# pcm5102_dac.net
KiCad netlist of a schematic drawn in EAGLE
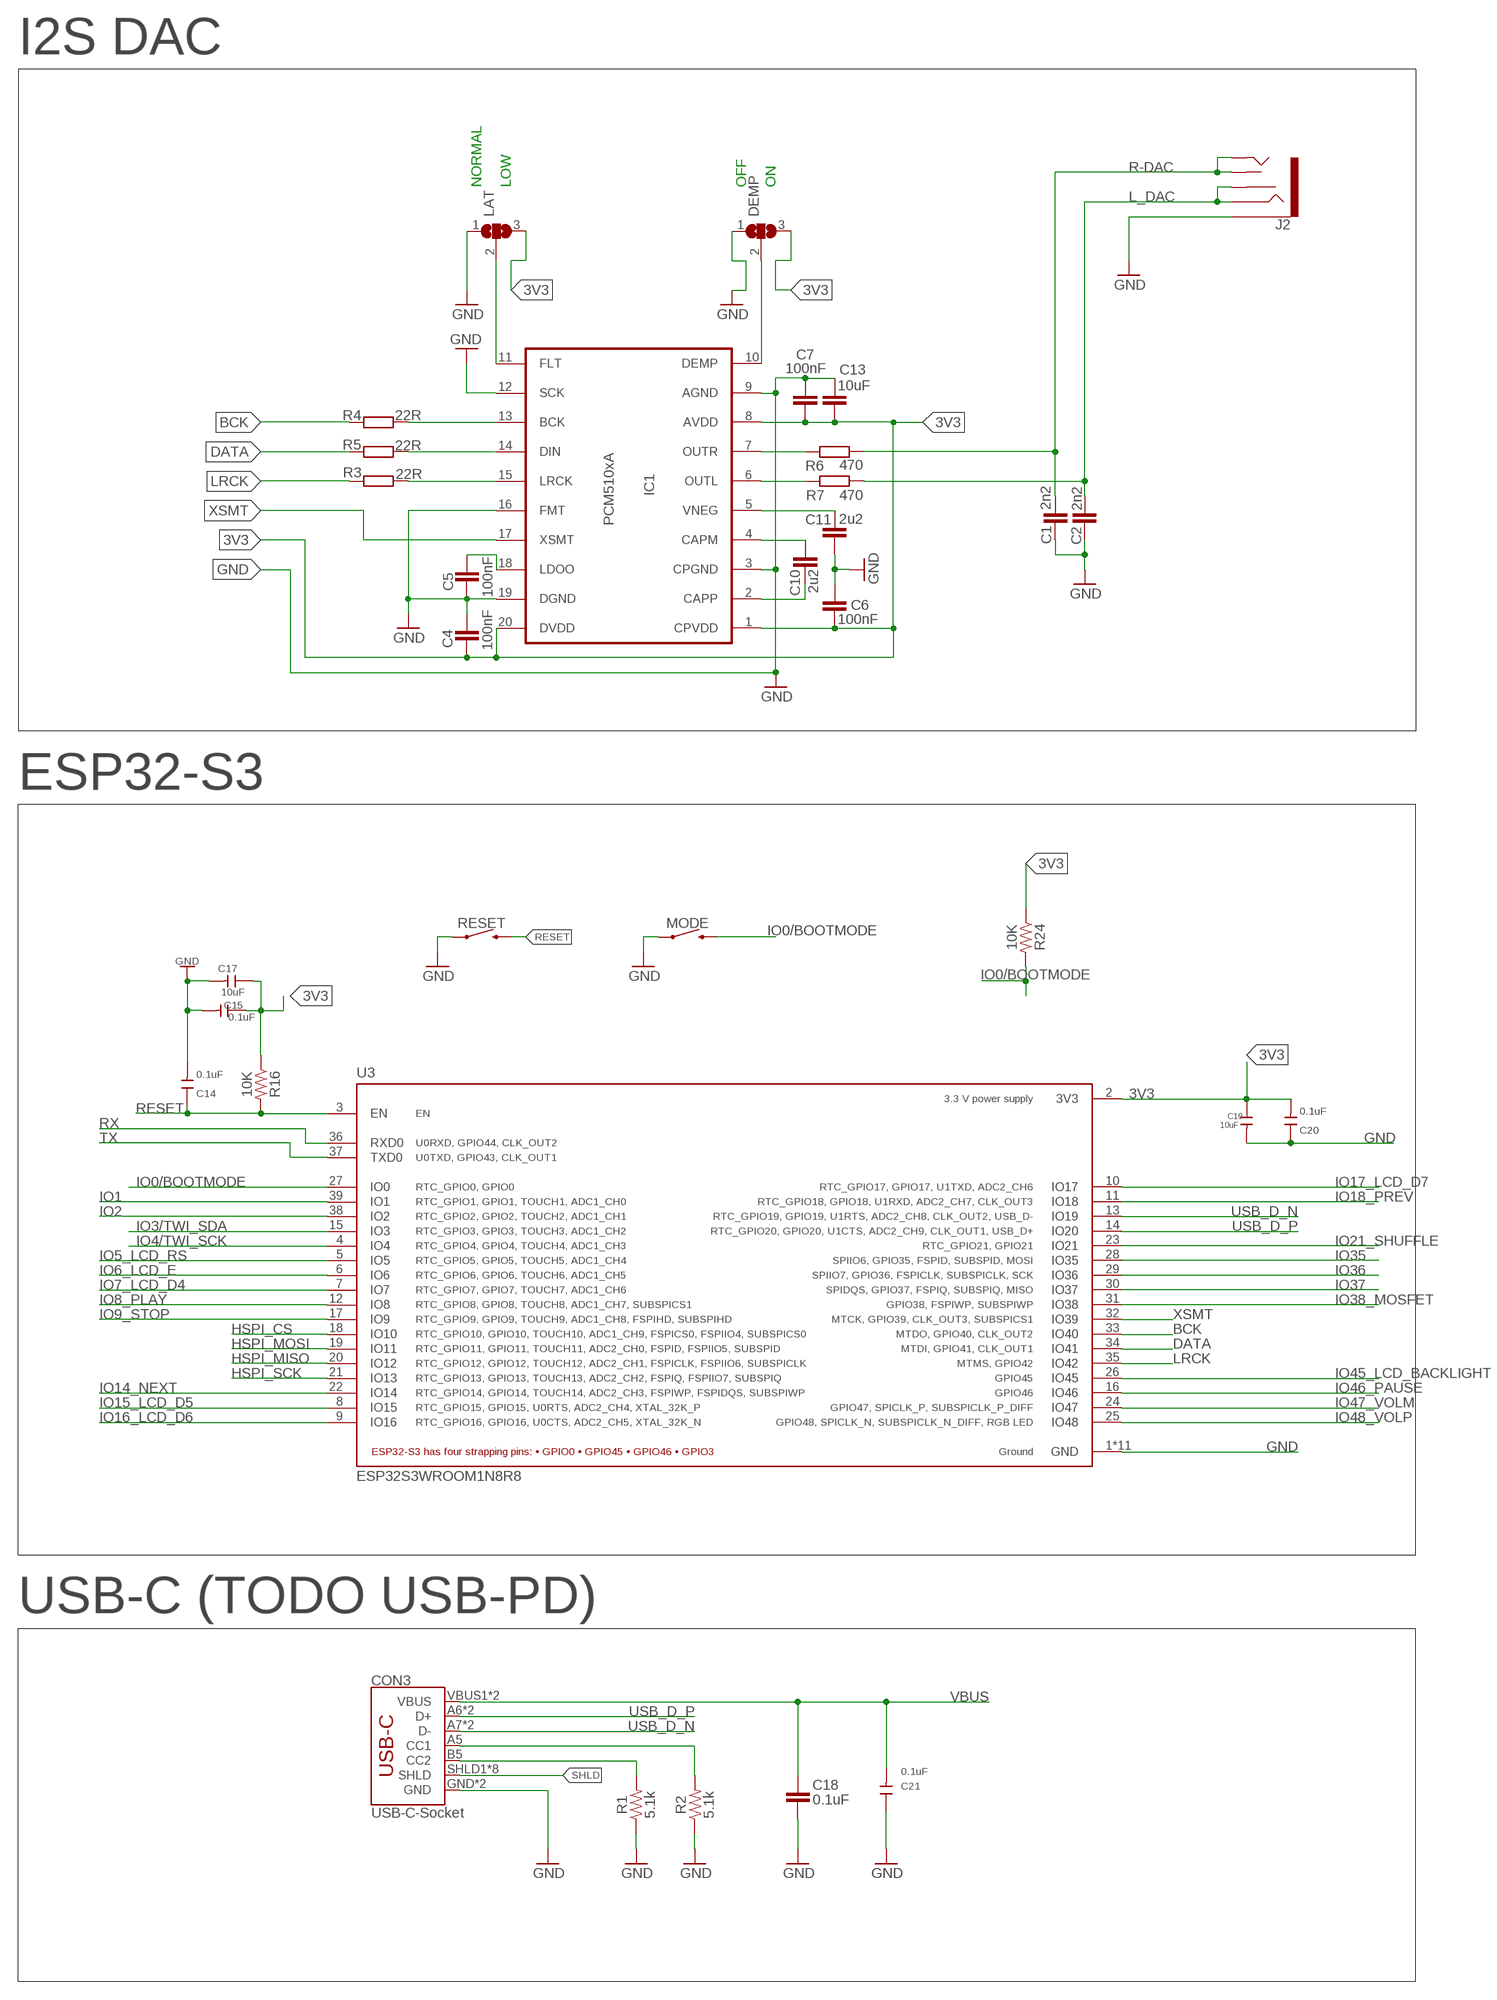
[diagram p0: schematic, sheet 1, part 1 of 3]
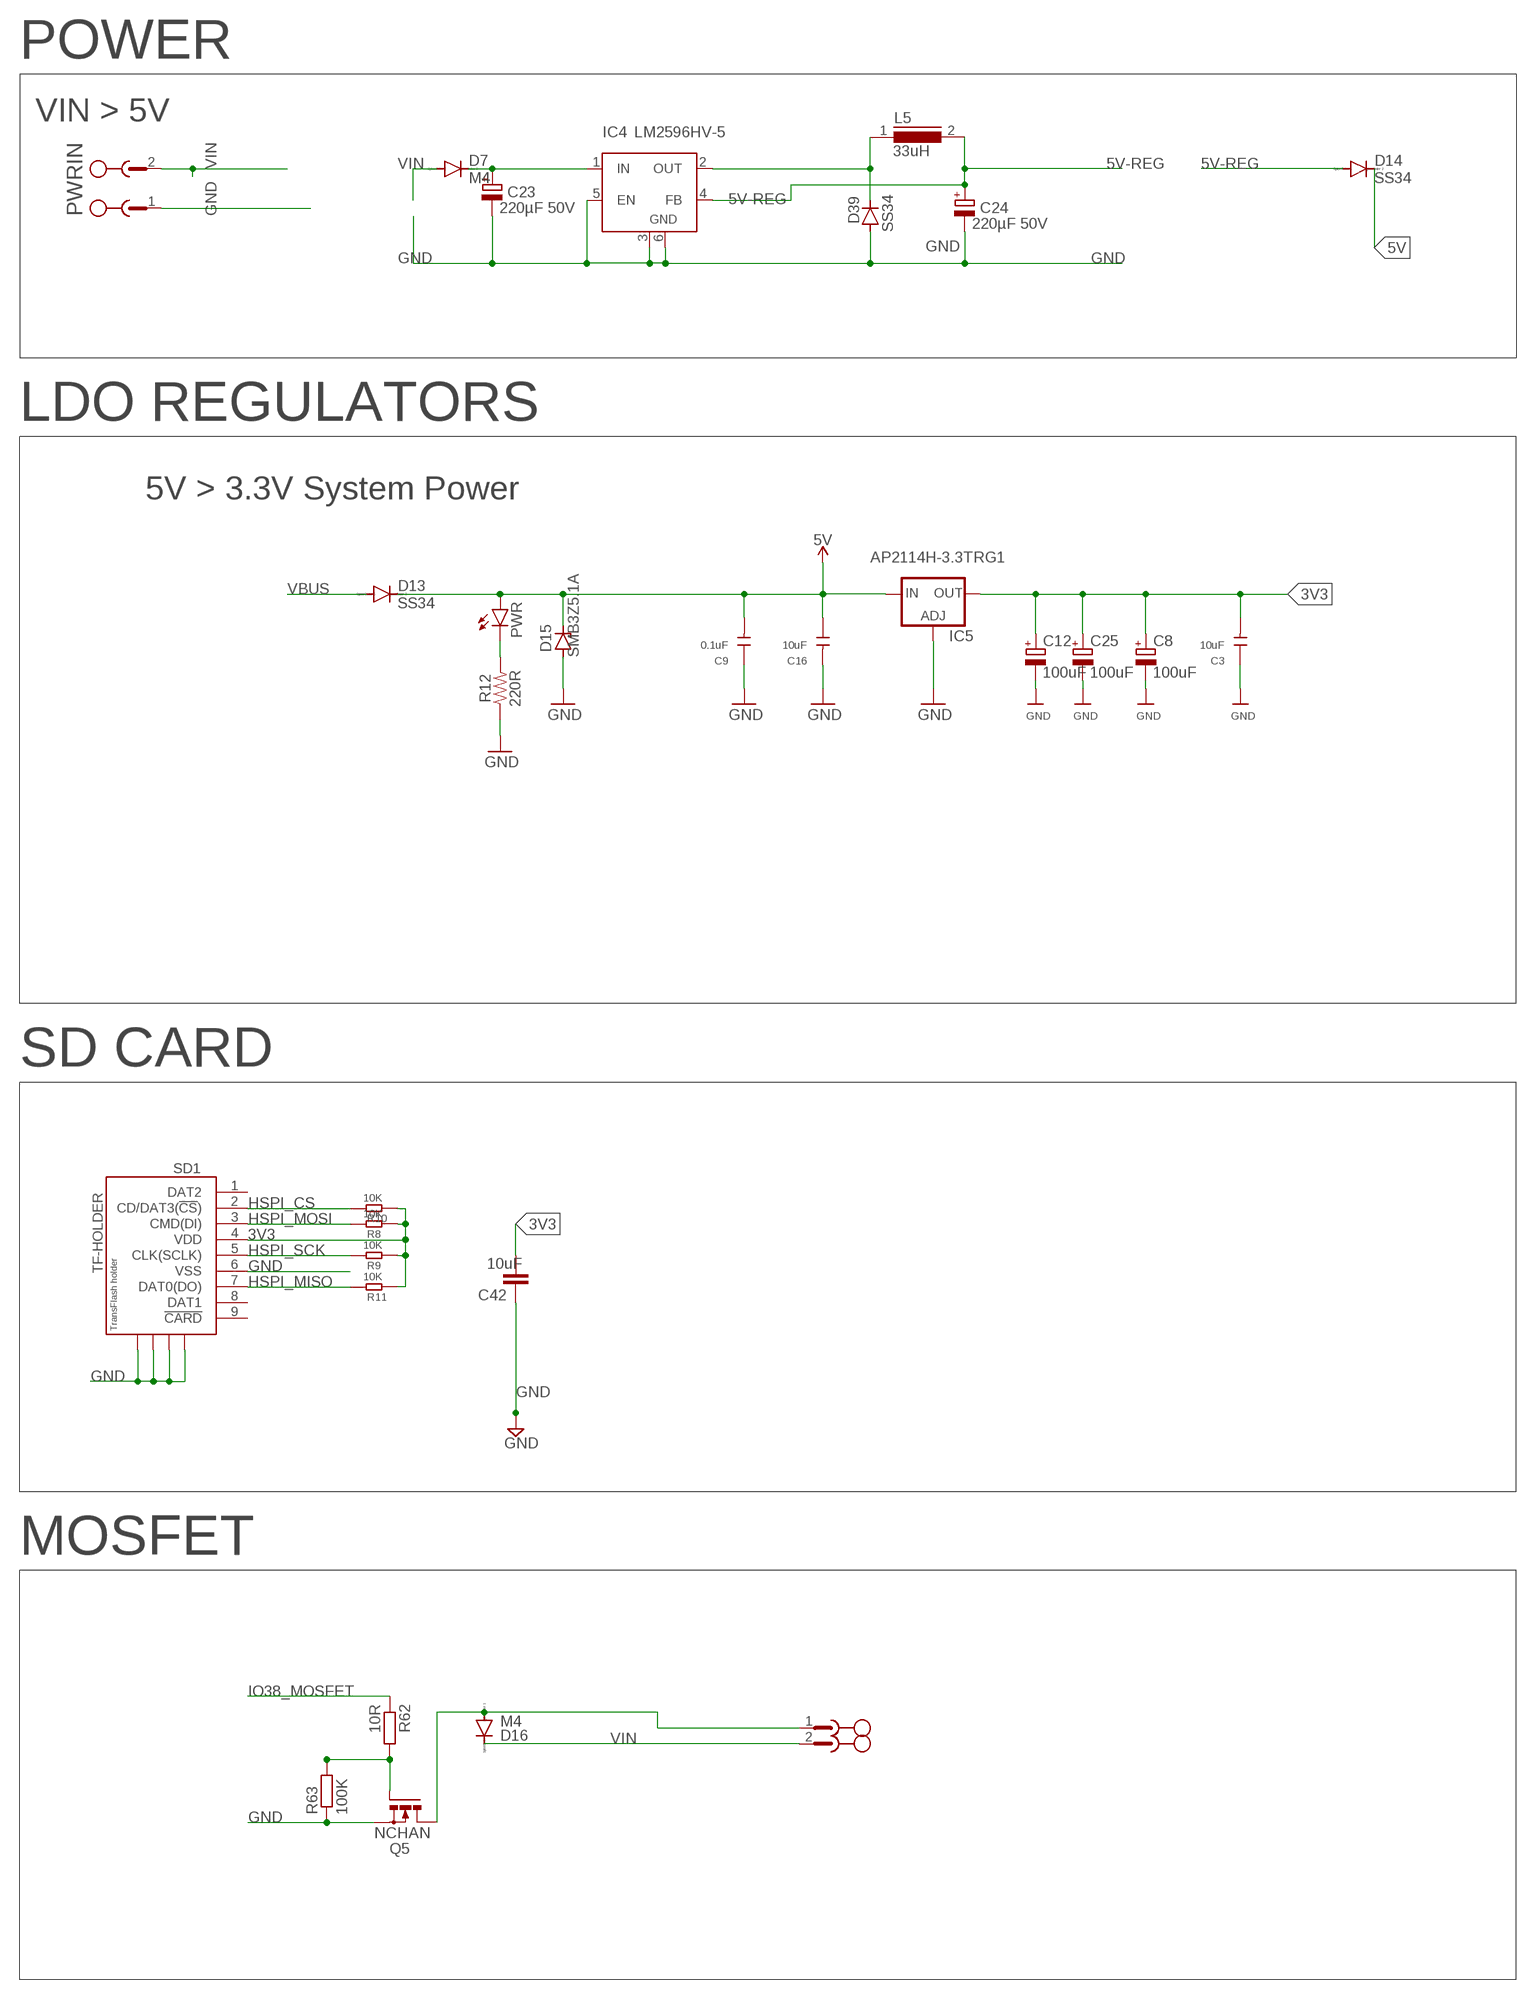
[diagram p1: schematic, sheet 1, part 2 of 3]
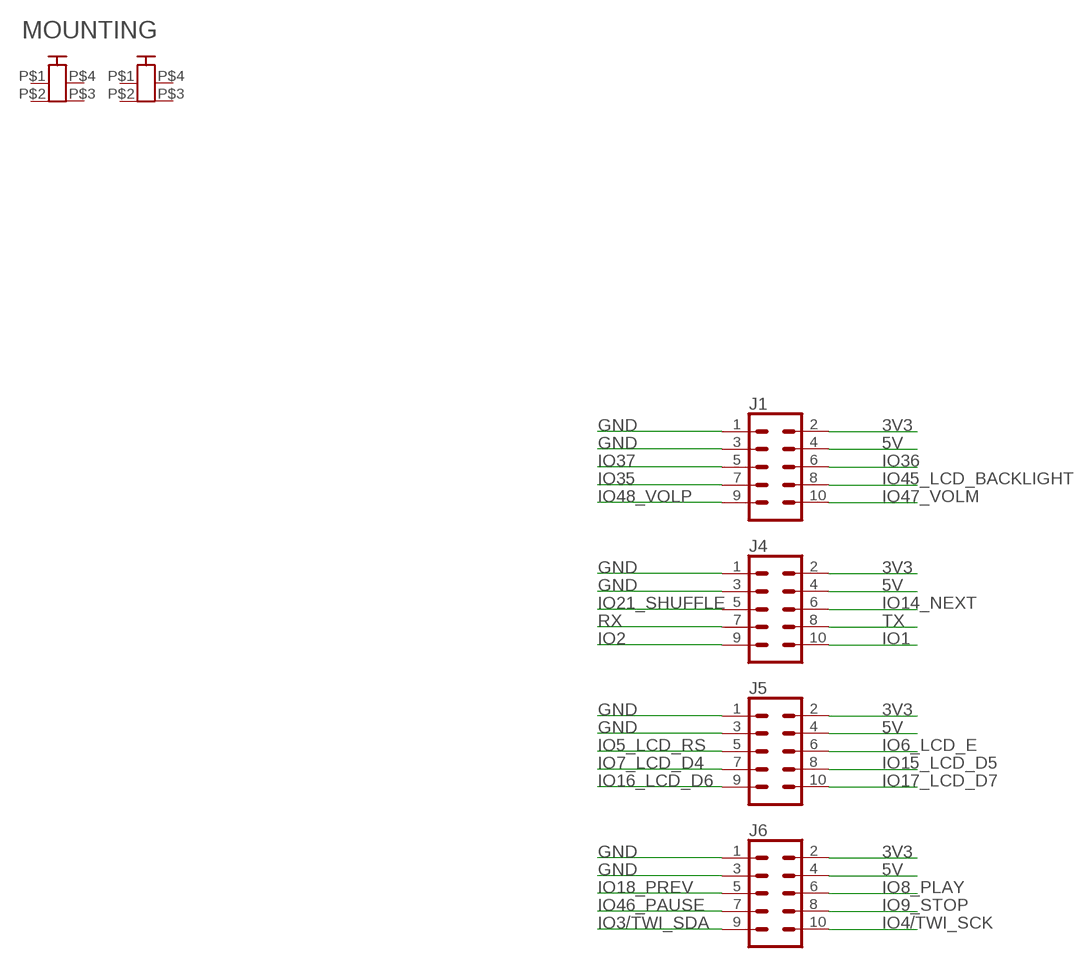
[diagram p2: schematic, sheet 1, part 3 of 3]

(export (version "E")
  (design (tool "Eeschema 10.0.6"))
  (components
    (comp (ref "C1")
      (value "2n2")
      (footprint "eagle-import:C1206")
      (libsource (lib "eagle-import") (part "C-EUC1206"))
    )
    (comp (ref "C2")
      (value "2n2")
      (footprint "eagle-import:C1206")
      (libsource (lib "eagle-import") (part "C-EUC1206"))
    )
    (comp (ref "C3")
      (value "10uF")
      (footprint "eagle-import:DISCRETE_C1206")
      (libsource (lib "eagle-import") (part "DISCRETE_C-1206"))
    )
    (comp (ref "C4")
      (value "100nF")
      (footprint "eagle-import:C1206")
      (libsource (lib "eagle-import") (part "C-EUC1206"))
    )
    (comp (ref "C5")
      (value "100nF")
      (footprint "eagle-import:C1206")
      (libsource (lib "eagle-import") (part "C-EUC1206"))
    )
    (comp (ref "C6")
      (value "100nF")
      (footprint "eagle-import:C1206")
      (libsource (lib "eagle-import") (part "C-EUC1206"))
    )
    (comp (ref "C7")
      (value "100nF")
      (footprint "eagle-import:C1206")
      (libsource (lib "eagle-import") (part "C-EUC1206"))
    )
    (comp (ref "C8")
      (value "100uF")
      (footprint "eagle-import:PANASONIC_D")
      (libsource (lib "eagle-import") (part "CPOL-EUD"))
    )
    (comp (ref "C9")
      (value "0.1uF")
      (footprint "eagle-import:DISCRETE_C0603")
      (libsource (lib "eagle-import") (part "DISCRETE_C-0603"))
    )
    (comp (ref "C10")
      (value "2u2")
      (footprint "eagle-import:C1206")
      (libsource (lib "eagle-import") (part "C-EUC1206"))
    )
    (comp (ref "C11")
      (value "2u2")
      (footprint "eagle-import:C1206")
      (libsource (lib "eagle-import") (part "C-EUC1206"))
    )
    (comp (ref "C12")
      (value "100uF")
      (footprint "eagle-import:PANASONIC_D")
      (libsource (lib "eagle-import") (part "CPOL-EUD"))
    )
    (comp (ref "C13")
      (value "10uF")
      (footprint "eagle-import:C1206")
      (libsource (lib "eagle-import") (part "C-EUC1206"))
    )
    (comp (ref "C14")
      (value "0.1uF")
      (footprint "eagle-import:DISCRETE_C0603")
      (libsource (lib "eagle-import") (part "DISCRETE_C-0603"))
    )
    (comp (ref "C15")
      (value "0.1uF")
      (footprint "eagle-import:DISCRETE_C0603")
      (libsource (lib "eagle-import") (part "DISCRETE_C-0603"))
    )
    (comp (ref "C16")
      (value "10uF")
      (footprint "eagle-import:C1206")
      (libsource (lib "eagle-import") (part "C-1206"))
    )
    (comp (ref "C17")
      (value "10uF")
      (footprint "eagle-import:DISCRETE_C1206")
      (libsource (lib "eagle-import") (part "DISCRETE_C-1206"))
    )
    (comp (ref "C18")
      (value "0.1uF")
      (footprint "eagle-import:0603-CAP")
      (libsource (lib "eagle-import") (part "CAP0603-CAP"))
    )
    (comp (ref "C19")
      (value "10uF")
      (footprint "eagle-import:C1206")
      (libsource (lib "eagle-import") (part "C-1206"))
    )
    (comp (ref "C20")
      (value "0.1uF")
      (footprint "eagle-import:DISCRETE_C0603")
      (libsource (lib "eagle-import") (part "DISCRETE_C-0603"))
    )
    (comp (ref "C21")
      (value "0.1uF")
      (footprint "eagle-import:DISCRETE_C0603")
      (libsource (lib "eagle-import") (part "DISCRETE_C-0603"))
    )
    (comp (ref "C23")
      (value "220µF 50V")
      (footprint "eagle-import:PANASONIC_E")
      (libsource (lib "eagle-import") (part "resistor_CPOL-EUE"))
    )
    (comp (ref "C24")
      (value "220µF 50V")
      (footprint "eagle-import:PANASONIC_E")
      (libsource (lib "eagle-import") (part "resistor_CPOL-EUE"))
    )
    (comp (ref "C25")
      (value "100uF")
      (footprint "eagle-import:PANASONIC_D")
      (libsource (lib "eagle-import") (part "CPOL-EUD"))
    )
    (comp (ref "C42")
      (value "10uF")
      (footprint "eagle-import:C1206")
      (libsource (lib "eagle-import") (part "resistor_C-EUC1206"))
    )
    (comp (ref "CON3")
      (value "USB-C-Socket")
      (footprint "eagle-import:USB-C-16P")
      (libsource (lib "eagle-import") (part "USB_C16PIN"))
    )
    (comp (ref "CON7")
      (value "PCB-2M3")
      (footprint "eagle-import:PCB2-M3")
      (libsource (lib "eagle-import") (part "PCB-2M3"))
    )
    (comp (ref "CON8")
      (value "PCB-2M3")
      (footprint "eagle-import:PCB2-M3")
      (libsource (lib "eagle-import") (part "PCB-2M3"))
    )
    (comp (ref "D7")
      (value "M4")
      (footprint "eagle-import:DO-214AC")
      (libsource (lib "eagle-import") (part "DIODE-DO-214AC"))
    )
    (comp (ref "D13")
      (value "SS34")
      (footprint "eagle-import:DO-214AC")
      (libsource (lib "eagle-import") (part "DIODE-DO-214AC"))
    )
    (comp (ref "D14")
      (value "SS34")
      (footprint "eagle-import:DO-214AC")
      (libsource (lib "eagle-import") (part "DIODE-DO-214AC"))
    )
    (comp (ref "D15")
      (value "SMB3Z5.1A")
      (footprint "eagle-import:SMB")
      (libsource (lib "eagle-import") (part "ZENER-DIODESMB"))
    )
    (comp (ref "D16")
      (value "M4")
      (footprint "eagle-import:DO-214AC")
      (libsource (lib "eagle-import") (part "DIODE-DO-214AC"))
    )
    (comp (ref "D39")
      (value "SS34")
      (footprint "eagle-import:SOD87")
      (libsource (lib "eagle-import") (part "D-SOD-87"))
    )
    (comp (ref "DEMP")
      (value "SJ2W")
      (footprint "eagle-import:SJ_2")
      (libsource (lib "eagle-import") (part "SJ2W"))
    )
    (comp (ref "IC1")
      (value "PCM510xA")
      (footprint "eagle-import:TSSOP20")
      (libsource (lib "eagle-import") (part "PCM510X"))
    )
    (comp (ref "IC4")
      (value "LM2596HV-5")
      (footprint "eagle-import:TO263-5")
      (libsource (lib "eagle-import") (part "LM2596S"))
    )
    (comp (ref "IC5")
      (value "AP2114H-3.3TRG1")
      (footprint "eagle-import:SOT223")
      (libsource (lib "eagle-import") (part "LD117A?S33TR"))
    )
    (comp (ref "J1")
      (value "CONN_05X2SHD")
      (footprint "eagle-import:2X5-SHROUDED")
      (libsource (lib "eagle-import") (part "CONN_05X2SHD"))
    )
    (comp (ref "J2")
      (value "AUDIO_JACK_3.5MM_PTH")
      (footprint "eagle-import:AUDIO-JACK")
      (libsource (lib "eagle-import") (part "AUDIO_JACK_3.5MM_PTH"))
    )
    (comp (ref "J4")
      (value "CONN_05X2SHD")
      (footprint "eagle-import:2X5-SHROUDED")
      (libsource (lib "eagle-import") (part "CONN_05X2SHD"))
    )
    (comp (ref "J5")
      (value "CONN_05X2SHD")
      (footprint "eagle-import:2X5-SHROUDED")
      (libsource (lib "eagle-import") (part "CONN_05X2SHD"))
    )
    (comp (ref "J6")
      (value "CONN_05X2SHD")
      (footprint "eagle-import:2X5-SHROUDED")
      (libsource (lib "eagle-import") (part "CONN_05X2SHD"))
    )
    (comp (ref "L5")
      (value "33uH")
      (footprint "eagle-import:DR127")
      (libsource (lib "eagle-import") (part "DR127"))
    )
    (comp (ref "LAT")
      (value "SJ2W")
      (footprint "eagle-import:SJ_2")
      (libsource (lib "eagle-import") (part "SJ2W"))
    )
    (comp (ref "MODE")
      (value "MOMENTARY-SWITCH-SPST-PTH-6.0MM")
      (footprint "eagle-import:TACTILE_SWITCH_PTH_6.0MM")
      (libsource (lib "eagle-import") (part "MOMENTARY-SWITCH-SPST-PTH-6.0MM"))
    )
    (comp (ref "PWR")
      (value "LED3MM")
      (footprint "eagle-import:LED3MM")
      (libsource (lib "eagle-import") (part "LED3MM"))
    )
    (comp (ref "PWRIN")
      (value "Phoenix Pluggable 5.08mm 2 way")
      (footprint "eagle-import:MSTBA2")
      (fields (field (name "MF") "FARNELL") (field (name "MPN") "1757242"))
      (libsource (lib "eagle-import") (part "MSTBA2"))
    )
    (comp (ref "Q5")
      (value "NCHAN")
      (footprint "eagle-import:D-PAK_TO252AA")
      (libsource (lib "eagle-import") (part "N-POWER-MOSFETDPAK-MOSFET"))
    )
    (comp (ref "R1")
      (value "5.1k")
      (footprint "eagle-import:0603@1")
      (libsource (lib "eagle-import") (part "5.1KOHM5.1KOHM-0603-1/10W-1%"))
    )
    (comp (ref "R2")
      (value "5.1k")
      (footprint "eagle-import:0603@1")
      (libsource (lib "eagle-import") (part "5.1KOHM5.1KOHM-0603-1/10W-1%"))
    )
    (comp (ref "R3")
      (value "22R")
      (footprint "eagle-import:R0805")
      (libsource (lib "eagle-import") (part "R-EU_R0805"))
    )
    (comp (ref "R4")
      (value "22R")
      (footprint "eagle-import:R0805")
      (libsource (lib "eagle-import") (part "R-EU_R0805"))
    )
    (comp (ref "R5")
      (value "22R")
      (footprint "eagle-import:R0805")
      (libsource (lib "eagle-import") (part "R-EU_R0805"))
    )
    (comp (ref "R6")
      (value "470")
      (footprint "eagle-import:R1206")
      (libsource (lib "eagle-import") (part "R-EU_R1206"))
    )
    (comp (ref "R7")
      (value "470")
      (footprint "eagle-import:R1206")
      (libsource (lib "eagle-import") (part "R-EU_R1206"))
    )
    (comp (ref "R8")
      (value "10K")
      (footprint "eagle-import:R0603")
      (libsource (lib "eagle-import") (part "R-0603"))
    )
    (comp (ref "R9")
      (value "10K")
      (footprint "eagle-import:R0603")
      (libsource (lib "eagle-import") (part "R-0603"))
    )
    (comp (ref "R10")
      (value "10K")
      (footprint "eagle-import:R0603")
      (libsource (lib "eagle-import") (part "R-0603"))
    )
    (comp (ref "R11")
      (value "10K")
      (footprint "eagle-import:R0603")
      (libsource (lib "eagle-import") (part "R-0603"))
    )
    (comp (ref "R12")
      (value "220R")
      (footprint "eagle-import:0603@1")
      (libsource (lib "eagle-import") (part "5.1KOHM5.1KOHM-0603-1/10W-1%"))
    )
    (comp (ref "R16")
      (value "10K")
      (footprint "eagle-import:0603@1")
      (libsource (lib "eagle-import") (part "5.1KOHM5.1KOHM-0603-1/10W-1%"))
    )
    (comp (ref "R24")
      (value "10K")
      (footprint "eagle-import:0603@1")
      (libsource (lib "eagle-import") (part "5.1KOHM5.1KOHM-0603-1/10W-1%"))
    )
    (comp (ref "R62")
      (value "10R")
      (footprint "eagle-import:R0603")
      (libsource (lib "eagle-import") (part "resistor_R-EU_R0603"))
    )
    (comp (ref "R63")
      (value "100K")
      (footprint "eagle-import:R0603")
      (libsource (lib "eagle-import") (part "resistor_R-EU_R0603"))
    )
    (comp (ref "RESET")
      (value "MOMENTARY-SWITCH-SPST-PTH-6.0MM")
      (footprint "eagle-import:TACTILE_SWITCH_PTH_6.0MM")
      (libsource (lib "eagle-import") (part "MOMENTARY-SWITCH-SPST-PTH-6.0MM"))
    )
    (comp (ref "SD1")
      (value "TF-HOLDER")
      (footprint "eagle-import:TF-PULL")
      (libsource (lib "eagle-import") (part "TF-HOLDER"))
    )
    (comp (ref "SWOUT")
      (value "Phoenix Pluggable 5.08mm 2 way")
      (footprint "eagle-import:MSTBA2")
      (fields (field (name "MF") "FARNELL") (field (name "MPN") "1757242"))
      (libsource (lib "eagle-import") (part "MSTBA2"))
    )
    (comp (ref "U3")
      (value "ESP32S3WROOM1N8R8")
      (footprint "eagle-import:XCVR_ESP32S3WROOM1N8R8")
      (fields (field (name "MF") "Espressif Systems"))
      (libsource (lib "eagle-import") (part "ESP32S3WROOM1N8R8"))
    )
  )
  (nets
    (net (code "1") (name "/5V-REG") (class "Default")
      (node (ref "C24") (pin "+") (pinfunction "+_+") (pintype "passive"))
      (node (ref "D14") (pin "A") (pinfunction "A_A") (pintype "passive"))
      (node (ref "IC4") (pin "4") (pinfunction "FB_4") (pintype "input"))
      (node (ref "L5") (pin "2") (pinfunction "2_2") (pintype "passive"))
    )
    (net (code "2") (name "/HSPI_CS") (class "Default")
      (node (ref "R10") (pin "2") (pinfunction "2_2") (pintype "passive"))
      (node (ref "SD1") (pin "2") (pinfunction "CD/DAT3(~{CS})_2") (pintype "bidirectional"))
      (node (ref "U3") (pin "18") (pinfunction "IO10_18") (pintype "bidirectional"))
    )
    (net (code "3") (name "/HSPI_MISO") (class "Default")
      (node (ref "R11") (pin "2") (pinfunction "2_2") (pintype "passive"))
      (node (ref "SD1") (pin "7") (pinfunction "DAT0(DO)_7") (pintype "bidirectional"))
      (node (ref "U3") (pin "20") (pinfunction "IO12_20") (pintype "bidirectional"))
    )
    (net (code "4") (name "/HSPI_MOSI") (class "Default")
      (node (ref "R8") (pin "2") (pinfunction "2_2") (pintype "passive"))
      (node (ref "SD1") (pin "3") (pinfunction "CMD(DI)_3") (pintype "bidirectional"))
      (node (ref "U3") (pin "19") (pinfunction "IO11_19") (pintype "bidirectional"))
    )
    (net (code "5") (name "/HSPI_SCK") (class "Default")
      (node (ref "R9") (pin "2") (pinfunction "2_2") (pintype "passive"))
      (node (ref "SD1") (pin "5") (pinfunction "CLK(SCLK)_5") (pintype "input"))
      (node (ref "U3") (pin "21") (pinfunction "IO13_21") (pintype "bidirectional"))
    )
    (net (code "6") (name "/IO0{slash}BOOTMODE") (class "Default")
      (node (ref "MODE") (pin "3") (pinfunction "2_3") (pintype "passive"))
      (node (ref "R24") (pin "2") (pinfunction "2_2") (pintype "passive"))
      (node (ref "U3") (pin "27") (pinfunction "IO0_27") (pintype "bidirectional"))
    )
    (net (code "7") (name "/IO1") (class "Default")
      (node (ref "J4") (pin "10") (pinfunction "10_10") (pintype "passive"))
      (node (ref "U3") (pin "39") (pinfunction "IO1_39") (pintype "bidirectional"))
    )
    (net (code "8") (name "/IO2") (class "Default")
      (node (ref "J4") (pin "9") (pinfunction "9_9") (pintype "passive"))
      (node (ref "U3") (pin "38") (pinfunction "IO2_38") (pintype "bidirectional"))
    )
    (net (code "9") (name "/IO3{slash}TWI_SDA") (class "Default")
      (node (ref "J6") (pin "9") (pinfunction "9_9") (pintype "passive"))
      (node (ref "U3") (pin "15") (pinfunction "IO3_15") (pintype "bidirectional"))
    )
    (net (code "10") (name "/IO4{slash}TWI_SCK") (class "Default")
      (node (ref "J6") (pin "10") (pinfunction "10_10") (pintype "passive"))
      (node (ref "U3") (pin "4") (pinfunction "IO4_4") (pintype "bidirectional"))
    )
    (net (code "11") (name "/IO5_LCD_RS") (class "Default")
      (node (ref "J5") (pin "5") (pinfunction "5_5") (pintype "passive"))
      (node (ref "U3") (pin "5") (pinfunction "IO5_5") (pintype "bidirectional"))
    )
    (net (code "12") (name "/IO6_LCD_E") (class "Default")
      (node (ref "J5") (pin "6") (pinfunction "6_6") (pintype "passive"))
      (node (ref "U3") (pin "6") (pinfunction "IO6_6") (pintype "bidirectional"))
    )
    (net (code "13") (name "/IO7_LCD_D4") (class "Default")
      (node (ref "J5") (pin "7") (pinfunction "7_7") (pintype "passive"))
      (node (ref "U3") (pin "7") (pinfunction "IO7_7") (pintype "bidirectional"))
    )
    (net (code "14") (name "/IO8_PLAY") (class "Default")
      (node (ref "J6") (pin "6") (pinfunction "6_6") (pintype "passive"))
      (node (ref "U3") (pin "12") (pinfunction "IO8_12") (pintype "bidirectional"))
    )
    (net (code "15") (name "/IO9_STOP") (class "Default")
      (node (ref "J6") (pin "8") (pinfunction "8_8") (pintype "passive"))
      (node (ref "U3") (pin "17") (pinfunction "IO9_17") (pintype "bidirectional"))
    )
    (net (code "16") (name "/IO14_NEXT") (class "Default")
      (node (ref "J4") (pin "6") (pinfunction "6_6") (pintype "passive"))
      (node (ref "U3") (pin "22") (pinfunction "IO14_22") (pintype "bidirectional"))
    )
    (net (code "17") (name "/IO15_LCD_D5") (class "Default")
      (node (ref "J5") (pin "8") (pinfunction "8_8") (pintype "passive"))
      (node (ref "U3") (pin "8") (pinfunction "IO15_8") (pintype "bidirectional"))
    )
    (net (code "18") (name "/IO16_LCD_D6") (class "Default")
      (node (ref "J5") (pin "9") (pinfunction "9_9") (pintype "passive"))
      (node (ref "U3") (pin "9") (pinfunction "IO16_9") (pintype "bidirectional"))
    )
    (net (code "19") (name "/IO17_LCD_D7") (class "Default")
      (node (ref "J5") (pin "10") (pinfunction "10_10") (pintype "passive"))
      (node (ref "U3") (pin "10") (pinfunction "IO17_10") (pintype "bidirectional"))
    )
    (net (code "20") (name "/IO18_PREV") (class "Default")
      (node (ref "J6") (pin "5") (pinfunction "5_5") (pintype "passive"))
      (node (ref "U3") (pin "11") (pinfunction "IO18_11") (pintype "bidirectional"))
    )
    (net (code "21") (name "/IO21_SHUFFLE") (class "Default")
      (node (ref "J4") (pin "5") (pinfunction "5_5") (pintype "passive"))
      (node (ref "U3") (pin "23") (pinfunction "IO21_23") (pintype "bidirectional"))
    )
    (net (code "22") (name "/IO35") (class "Default")
      (node (ref "J1") (pin "7") (pinfunction "7_7") (pintype "passive"))
      (node (ref "U3") (pin "28") (pinfunction "IO35_28") (pintype "bidirectional"))
    )
    (net (code "23") (name "/IO36") (class "Default")
      (node (ref "J1") (pin "6") (pinfunction "6_6") (pintype "passive"))
      (node (ref "U3") (pin "29") (pinfunction "IO36_29") (pintype "bidirectional"))
    )
    (net (code "24") (name "/IO37") (class "Default")
      (node (ref "J1") (pin "5") (pinfunction "5_5") (pintype "passive"))
      (node (ref "U3") (pin "30") (pinfunction "IO37_30") (pintype "bidirectional"))
    )
    (net (code "25") (name "/IO38_MOSFET") (class "Default")
      (node (ref "R62") (pin "1") (pinfunction "1_1") (pintype "passive"))
      (node (ref "U3") (pin "31") (pinfunction "IO38_31") (pintype "bidirectional"))
    )
    (net (code "26") (name "/IO45_LCD_BACKLIGHT") (class "Default")
      (node (ref "J1") (pin "8") (pinfunction "8_8") (pintype "passive"))
      (node (ref "U3") (pin "26") (pinfunction "IO45_26") (pintype "bidirectional"))
    )
    (net (code "27") (name "/IO46_PAUSE") (class "Default")
      (node (ref "J6") (pin "7") (pinfunction "7_7") (pintype "passive"))
      (node (ref "U3") (pin "16") (pinfunction "IO46_16") (pintype "bidirectional"))
    )
    (net (code "28") (name "/IO47_VOLM") (class "Default")
      (node (ref "J1") (pin "10") (pinfunction "10_10") (pintype "passive"))
      (node (ref "U3") (pin "24") (pinfunction "IO47_24") (pintype "bidirectional"))
    )
    (net (code "29") (name "/IO48_VOLP") (class "Default")
      (node (ref "J1") (pin "9") (pinfunction "9_9") (pintype "passive"))
      (node (ref "U3") (pin "25") (pinfunction "IO48_25") (pintype "bidirectional"))
    )
    (net (code "30") (name "/L_DAC") (class "Default")
      (node (ref "C2") (pin "1") (pinfunction "1_1") (pintype "passive"))
      (node (ref "J2") (pin "RING") (pinfunction "RING_RING") (pintype "bidirectional"))
      (node (ref "J2") (pin "RSH") (pinfunction "RSH_RSH") (pintype "bidirectional"))
      (node (ref "R7") (pin "2") (pinfunction "2_2") (pintype "passive"))
    )
    (net (code "31") (name "/R-DAC") (class "Default")
      (node (ref "C1") (pin "1") (pinfunction "1_1") (pintype "passive"))
      (node (ref "J2") (pin "TIP") (pinfunction "TIP_TIP") (pintype "bidirectional"))
      (node (ref "J2") (pin "TSH") (pinfunction "TSH_TSH") (pintype "bidirectional"))
      (node (ref "R6") (pin "2") (pinfunction "2_2") (pintype "passive"))
    )
    (net (code "32") (name "/RX") (class "Default")
      (node (ref "J4") (pin "7") (pinfunction "7_7") (pintype "passive"))
      (node (ref "U3") (pin "36") (pinfunction "RXD0_36") (pintype "bidirectional"))
    )
    (net (code "33") (name "/TX") (class "Default")
      (node (ref "J4") (pin "8") (pinfunction "8_8") (pintype "passive"))
      (node (ref "U3") (pin "37") (pinfunction "TXD0_37") (pintype "bidirectional"))
    )
    (net (code "34") (name "/USB_D_N") (class "Default")
      (node (ref "CON3") (pin "A7") (pinfunction "D-_A7") (pintype "bidirectional"))
      (node (ref "CON3") (pin "B7") (pinfunction "D-_B7") (pintype "bidirectional"))
      (node (ref "U3") (pin "13") (pinfunction "IO19_13") (pintype "bidirectional"))
    )
    (net (code "35") (name "/USB_D_P") (class "Default")
      (node (ref "CON3") (pin "A6") (pinfunction "D+_A6") (pintype "bidirectional"))
      (node (ref "CON3") (pin "B6") (pinfunction "D+_B6") (pintype "bidirectional"))
      (node (ref "U3") (pin "14") (pinfunction "IO20_14") (pintype "bidirectional"))
    )
    (net (code "36") (name "/VBUS") (class "Default")
      (node (ref "C18") (pin "1") (pinfunction "1_1") (pintype "passive"))
      (node (ref "C21") (pin "2") (pinfunction "2_2") (pintype "passive"))
      (node (ref "CON3") (pin "VBUS1") (pinfunction "VBUS_VBUS1") (pintype "bidirectional"))
      (node (ref "CON3") (pin "VBUS2") (pinfunction "VBUS_VBUS2") (pintype "bidirectional"))
      (node (ref "D13") (pin "A") (pinfunction "A_A") (pintype "passive"))
    )
    (net (code "37") (name "/VIN") (class "Default")
      (node (ref "D16") (pin "C") (pinfunction "C_C") (pintype "passive"))
      (node (ref "D7") (pin "A") (pinfunction "A_A") (pintype "passive"))
      (node (ref "PWRIN") (pin "2") (pinfunction "1_2") (pintype "passive"))
      (node (ref "SWOUT") (pin "2") (pinfunction "1_2") (pintype "passive"))
    )
    (net (code "38") (name "3V3") (class "Default")
      (node (ref "C12") (pin "+") (pinfunction "+_+") (pintype "passive"))
      (node (ref "C13") (pin "2") (pinfunction "2_2") (pintype "passive"))
      (node (ref "C15") (pin "1") (pinfunction "1_1") (pintype "passive"))
      (node (ref "C17") (pin "1") (pinfunction "1_1") (pintype "passive"))
      (node (ref "C19") (pin "1") (pinfunction "1_1") (pintype "passive"))
      (node (ref "C20") (pin "2") (pinfunction "2_2") (pintype "passive"))
      (node (ref "C25") (pin "+") (pinfunction "+_+") (pintype "passive"))
      (node (ref "C3") (pin "2") (pinfunction "2_2") (pintype "passive"))
      (node (ref "C4") (pin "2") (pinfunction "2_2") (pintype "passive"))
      (node (ref "C42") (pin "2") (pinfunction "2_2") (pintype "passive"))
      (node (ref "C6") (pin "2") (pinfunction "2_2") (pintype "passive"))
      (node (ref "C7") (pin "2") (pinfunction "2_2") (pintype "passive"))
      (node (ref "C8") (pin "+") (pinfunction "+_+") (pintype "passive"))
      (node (ref "DEMP") (pin "3") (pinfunction "3_3") (pintype "passive"))
      (node (ref "IC1") (pin "1") (pinfunction "CPVDD_1") (pintype "power_in"))
      (node (ref "IC1") (pin "20") (pinfunction "DVDD_20") (pintype "power_in"))
      (node (ref "IC1") (pin "8") (pinfunction "AVDD_8") (pintype "power_in"))
      (node (ref "IC5") (pin "4") (pinfunction "OUT_4") (pintype "passive"))
      (node (ref "J1") (pin "2") (pinfunction "2_2") (pintype "passive"))
      (node (ref "J4") (pin "2") (pinfunction "2_2") (pintype "passive"))
      (node (ref "J5") (pin "2") (pinfunction "2_2") (pintype "passive"))
      (node (ref "J6") (pin "2") (pinfunction "2_2") (pintype "passive"))
      (node (ref "LAT") (pin "3") (pinfunction "3_3") (pintype "passive"))
      (node (ref "R10") (pin "1") (pinfunction "1_1") (pintype "passive"))
      (node (ref "R11") (pin "1") (pinfunction "1_1") (pintype "passive"))
      (node (ref "R16") (pin "1") (pinfunction "1_1") (pintype "passive"))
      (node (ref "R24") (pin "1") (pinfunction "1_1") (pintype "passive"))
      (node (ref "R8") (pin "1") (pinfunction "1_1") (pintype "passive"))
      (node (ref "R9") (pin "1") (pinfunction "1_1") (pintype "passive"))
      (node (ref "SD1") (pin "4") (pinfunction "VDD_4") (pintype "power_in"))
      (node (ref "U3") (pin "2") (pinfunction "3V3_2") (pintype "power_in"))
    )
    (net (code "39") (name "5V") (class "Default")
      (node (ref "C16") (pin "1") (pinfunction "1_1") (pintype "passive"))
      (node (ref "C9") (pin "2") (pinfunction "2_2") (pintype "passive"))
      (node (ref "D13") (pin "C") (pinfunction "C_C") (pintype "passive"))
      (node (ref "D14") (pin "C") (pinfunction "C_C") (pintype "passive"))
      (node (ref "D15") (pin "C") (pinfunction "C_C") (pintype "passive"))
      (node (ref "IC5") (pin "3") (pinfunction "IN_3") (pintype "input"))
      (node (ref "J1") (pin "4") (pinfunction "4_4") (pintype "passive"))
      (node (ref "J4") (pin "4") (pinfunction "4_4") (pintype "passive"))
      (node (ref "J5") (pin "4") (pinfunction "4_4") (pintype "passive"))
      (node (ref "J6") (pin "4") (pinfunction "4_4") (pintype "passive"))
      (node (ref "PWR") (pin "A") (pinfunction "A_A") (pintype "passive"))
    )
    (net (code "40") (name "BCK") (class "Default")
      (node (ref "R4") (pin "1") (pinfunction "1_1") (pintype "passive"))
      (node (ref "U3") (pin "33") (pinfunction "IO40_33") (pintype "bidirectional"))
    )
    (net (code "41") (name "DATA") (class "Default")
      (node (ref "R5") (pin "1") (pinfunction "1_1") (pintype "passive"))
      (node (ref "U3") (pin "34") (pinfunction "IO41_34") (pintype "bidirectional"))
    )
    (net (code "42") (name "GND") (class "Default")
      (node (ref "C1") (pin "2") (pinfunction "2_2") (pintype "passive"))
      (node (ref "C11") (pin "2") (pinfunction "2_2") (pintype "passive"))
      (node (ref "C12") (pin "-") (pinfunction "-_-") (pintype "passive"))
      (node (ref "C13") (pin "1") (pinfunction "1_1") (pintype "passive"))
      (node (ref "C14") (pin "2") (pinfunction "2_2") (pintype "passive"))
      (node (ref "C15") (pin "2") (pinfunction "2_2") (pintype "passive"))
      (node (ref "C16") (pin "2") (pinfunction "2_2") (pintype "passive"))
      (node (ref "C17") (pin "2") (pinfunction "2_2") (pintype "passive"))
      (node (ref "C18") (pin "2") (pinfunction "2_2") (pintype "passive"))
      (node (ref "C19") (pin "2") (pinfunction "2_2") (pintype "passive"))
      (node (ref "C2") (pin "2") (pinfunction "2_2") (pintype "passive"))
      (node (ref "C20") (pin "1") (pinfunction "1_1") (pintype "passive"))
      (node (ref "C21") (pin "1") (pinfunction "1_1") (pintype "passive"))
      (node (ref "C23") (pin "-") (pinfunction "-_-") (pintype "passive"))
      (node (ref "C24") (pin "-") (pinfunction "-_-") (pintype "passive"))
      (node (ref "C25") (pin "-") (pinfunction "-_-") (pintype "passive"))
      (node (ref "C3") (pin "1") (pinfunction "1_1") (pintype "passive"))
      (node (ref "C4") (pin "1") (pinfunction "1_1") (pintype "passive"))
      (node (ref "C42") (pin "1") (pinfunction "1_1") (pintype "passive"))
      (node (ref "C5") (pin "2") (pinfunction "2_2") (pintype "passive"))
      (node (ref "C6") (pin "1") (pinfunction "1_1") (pintype "passive"))
      (node (ref "C7") (pin "1") (pinfunction "1_1") (pintype "passive"))
      (node (ref "C8") (pin "-") (pinfunction "-_-") (pintype "passive"))
      (node (ref "C9") (pin "1") (pinfunction "1_1") (pintype "passive"))
      (node (ref "CON3") (pin "GND") (pinfunction "GND_GND") (pintype "bidirectional"))
      (node (ref "CON3") (pin "GND2") (pinfunction "GND_GND2") (pintype "bidirectional"))
      (node (ref "D15") (pin "A") (pinfunction "A_A") (pintype "passive"))
      (node (ref "D39") (pin "2") (pinfunction "A_2") (pintype "passive"))
      (node (ref "DEMP") (pin "1") (pinfunction "1_1") (pintype "passive"))
      (node (ref "IC1") (pin "12") (pinfunction "SCK_12") (pintype "input"))
      (node (ref "IC1") (pin "16") (pinfunction "FMT_16") (pintype "input"))
      (node (ref "IC1") (pin "19") (pinfunction "DGND_19") (pintype "power_in"))
      (node (ref "IC1") (pin "3") (pinfunction "CPGND_3") (pintype "power_in"))
      (node (ref "IC1") (pin "9") (pinfunction "AGND_9") (pintype "power_in"))
      (node (ref "IC4") (pin "3") (pinfunction "GND_3") (pintype "power_in"))
      (node (ref "IC4") (pin "5") (pinfunction "EN_5") (pintype "input"))
      (node (ref "IC4") (pin "6") (pinfunction "GND_6") (pintype "power_in"))
      (node (ref "IC5") (pin "1") (pinfunction "ADJ_1") (pintype "input"))
      (node (ref "J1") (pin "1") (pinfunction "1_1") (pintype "passive"))
      (node (ref "J1") (pin "3") (pinfunction "3_3") (pintype "passive"))
      (node (ref "J2") (pin "SLEEVE") (pinfunction "SLEEVE_SLEEVE") (pintype "bidirectional"))
      (node (ref "J4") (pin "1") (pinfunction "1_1") (pintype "passive"))
      (node (ref "J4") (pin "3") (pinfunction "3_3") (pintype "passive"))
      (node (ref "J5") (pin "1") (pinfunction "1_1") (pintype "passive"))
      (node (ref "J5") (pin "3") (pinfunction "3_3") (pintype "passive"))
      (node (ref "J6") (pin "1") (pinfunction "1_1") (pintype "passive"))
      (node (ref "J6") (pin "3") (pinfunction "3_3") (pintype "passive"))
      (node (ref "LAT") (pin "1") (pinfunction "1_1") (pintype "passive"))
      (node (ref "MODE") (pin "1") (pinfunction "1_1") (pintype "passive"))
      (node (ref "PWRIN") (pin "1") (pinfunction "1_1") (pintype "passive"))
      (node (ref "Q5") (pin "3") (pinfunction "S_3") (pintype "passive"))
      (node (ref "R1") (pin "1") (pinfunction "1_1") (pintype "passive"))
      (node (ref "R12") (pin "1") (pinfunction "1_1") (pintype "passive"))
      (node (ref "R2") (pin "1") (pinfunction "1_1") (pintype "passive"))
      (node (ref "R63") (pin "1") (pinfunction "1_1") (pintype "passive"))
      (node (ref "RESET") (pin "1") (pinfunction "1_1") (pintype "passive"))
      (node (ref "SD1") (pin "6") (pinfunction "VSS_6") (pintype "power_in"))
      (node (ref "SD1") (pin "S1") (pinfunction "S1_S1") (pintype "passive"))
      (node (ref "SD1") (pin "S2") (pinfunction "S2_S2") (pintype "passive"))
      (node (ref "SD1") (pin "S3") (pinfunction "S3_S3") (pintype "passive"))
      (node (ref "SD1") (pin "S4") (pinfunction "S4_S4") (pintype "passive"))
      (node (ref "U3") (pin "1") (pinfunction "GND_1") (pintype "power_in"))
      (node (ref "U3") (pin "40") (pinfunction "GND_40") (pintype "power_in"))
      (node (ref "U3") (pin "41_1") (pinfunction "GND_41_1") (pintype "power_in"))
      (node (ref "U3") (pin "41_2") (pinfunction "GND_41_2") (pintype "power_in"))
      (node (ref "U3") (pin "41_3") (pinfunction "GND_41_3") (pintype "power_in"))
      (node (ref "U3") (pin "41_4") (pinfunction "GND_41_4") (pintype "power_in"))
      (node (ref "U3") (pin "41_5") (pinfunction "GND_41_5") (pintype "power_in"))
      (node (ref "U3") (pin "41_6") (pinfunction "GND_41_6") (pintype "power_in"))
      (node (ref "U3") (pin "41_7") (pinfunction "GND_41_7") (pintype "power_in"))
      (node (ref "U3") (pin "41_8") (pinfunction "GND_41_8") (pintype "power_in"))
      (node (ref "U3") (pin "41_9") (pinfunction "GND_41_9") (pintype "power_in"))
    )
    (net (code "43") (name "LRCK") (class "Default")
      (node (ref "R3") (pin "1") (pinfunction "1_1") (pintype "passive"))
      (node (ref "U3") (pin "35") (pinfunction "IO42_35") (pintype "bidirectional"))
    )
    (net (code "44") (name "Net-(CON3-CC1)") (class "Default")
      (node (ref "CON3") (pin "A5") (pinfunction "CC1_A5") (pintype "bidirectional"))
      (node (ref "R2") (pin "2") (pinfunction "2_2") (pintype "passive"))
    )
    (net (code "45") (name "Net-(CON3-CC2)") (class "Default")
      (node (ref "CON3") (pin "B5") (pinfunction "CC2_B5") (pintype "bidirectional"))
      (node (ref "R1") (pin "2") (pinfunction "2_2") (pintype "passive"))
    )
    (net (code "46") (name "Net-(D39-C)") (class "Default")
      (node (ref "D39") (pin "1") (pinfunction "C_1") (pintype "passive"))
      (node (ref "IC4") (pin "2") (pinfunction "OUT_2") (pintype "output"))
      (node (ref "L5") (pin "1") (pinfunction "1_1") (pintype "passive"))
    )
    (net (code "47") (name "Net-(IC1-BCK)") (class "Default")
      (node (ref "IC1") (pin "13") (pinfunction "BCK_13") (pintype "input"))
      (node (ref "R4") (pin "2") (pinfunction "2_2") (pintype "passive"))
    )
    (net (code "48") (name "Net-(IC1-CAPM)") (class "Default")
      (node (ref "C10") (pin "1") (pinfunction "1_1") (pintype "passive"))
      (node (ref "IC1") (pin "4") (pinfunction "CAPM_4") (pintype "output"))
    )
    (net (code "49") (name "Net-(IC1-CAPP)") (class "Default")
      (node (ref "C10") (pin "2") (pinfunction "2_2") (pintype "passive"))
      (node (ref "IC1") (pin "2") (pinfunction "CAPP_2") (pintype "output"))
    )
    (net (code "50") (name "Net-(IC1-DEMP)") (class "Default")
      (node (ref "DEMP") (pin "2") (pinfunction "2_2") (pintype "passive"))
      (node (ref "IC1") (pin "10") (pinfunction "DEMP_10") (pintype "input"))
    )
    (net (code "51") (name "Net-(IC1-DIN)") (class "Default")
      (node (ref "IC1") (pin "14") (pinfunction "DIN_14") (pintype "input"))
      (node (ref "R5") (pin "2") (pinfunction "2_2") (pintype "passive"))
    )
    (net (code "52") (name "Net-(IC1-FLT)") (class "Default")
      (node (ref "IC1") (pin "11") (pinfunction "FLT_11") (pintype "input"))
      (node (ref "LAT") (pin "2") (pinfunction "2_2") (pintype "passive"))
    )
    (net (code "53") (name "Net-(IC1-LDOO)") (class "Default")
      (node (ref "C5") (pin "1") (pinfunction "1_1") (pintype "passive"))
      (node (ref "IC1") (pin "18") (pinfunction "LDOO_18") (pintype "power_in"))
    )
    (net (code "54") (name "Net-(IC1-LRCK)") (class "Default")
      (node (ref "IC1") (pin "15") (pinfunction "LRCK_15") (pintype "input"))
      (node (ref "R3") (pin "2") (pinfunction "2_2") (pintype "passive"))
    )
    (net (code "55") (name "Net-(IC1-OUTL)") (class "Default")
      (node (ref "IC1") (pin "6") (pinfunction "OUTL_6") (pintype "output"))
      (node (ref "R7") (pin "1") (pinfunction "1_1") (pintype "passive"))
    )
    (net (code "56") (name "Net-(IC1-OUTR)") (class "Default")
      (node (ref "IC1") (pin "7") (pinfunction "OUTR_7") (pintype "output"))
      (node (ref "R6") (pin "1") (pinfunction "1_1") (pintype "passive"))
    )
    (net (code "57") (name "Net-(IC1-VNEG)") (class "Default")
      (node (ref "C11") (pin "1") (pinfunction "1_1") (pintype "passive"))
      (node (ref "IC1") (pin "5") (pinfunction "VNEG_5") (pintype "output"))
    )
    (net (code "58") (name "Net-(IC4-IN)") (class "Default")
      (node (ref "C23") (pin "+") (pinfunction "+_+") (pintype "passive"))
      (node (ref "D7") (pin "C") (pinfunction "C_C") (pintype "passive"))
      (node (ref "IC4") (pin "1") (pinfunction "IN_1") (pintype "input"))
    )
    (net (code "59") (name "Net-(PWR-C)") (class "Default")
      (node (ref "PWR") (pin "K") (pinfunction "C_K") (pintype "passive"))
      (node (ref "R12") (pin "2") (pinfunction "2_2") (pintype "passive"))
    )
    (net (code "60") (name "Net-(Q5-D)") (class "Default")
      (node (ref "D16") (pin "A") (pinfunction "A_A") (pintype "passive"))
      (node (ref "Q5") (pin "4") (pinfunction "D_4") (pintype "passive"))
      (node (ref "SWOUT") (pin "1") (pinfunction "1_1") (pintype "passive"))
    )
    (net (code "61") (name "Net-(Q5-G)") (class "Default")
      (node (ref "Q5") (pin "1") (pinfunction "G_1") (pintype "passive"))
      (node (ref "R62") (pin "2") (pinfunction "2_2") (pintype "passive"))
      (node (ref "R63") (pin "2") (pinfunction "2_2") (pintype "passive"))
    )
    (net (code "62") (name "RESET") (class "Default")
      (node (ref "C14") (pin "1") (pinfunction "1_1") (pintype "passive"))
      (node (ref "R16") (pin "2") (pinfunction "2_2") (pintype "passive"))
      (node (ref "RESET") (pin "3") (pinfunction "2_3") (pintype "passive"))
      (node (ref "U3") (pin "3") (pinfunction "EN_3") (pintype "input"))
    )
    (net (code "63") (name "SHLD") (class "Default")
      (node (ref "CON3") (pin "SHLD1") (pinfunction "SHLD_SHLD1") (pintype "bidirectional"))
      (node (ref "CON3") (pin "SHLD2") (pinfunction "SHLD_SHLD2") (pintype "bidirectional"))
      (node (ref "CON3") (pin "SHLD3") (pinfunction "SHLD_SHLD3") (pintype "bidirectional"))
      (node (ref "CON3") (pin "SHLD4") (pinfunction "SHLD_SHLD4") (pintype "bidirectional"))
      (node (ref "CON3") (pin "SHLD5") (pinfunction "SHLD_SHLD5") (pintype "bidirectional"))
      (node (ref "CON3") (pin "SHLD6") (pinfunction "SHLD_SHLD6") (pintype "bidirectional"))
      (node (ref "CON3") (pin "SHLD7") (pinfunction "SHLD_SHLD7") (pintype "bidirectional"))
      (node (ref "CON3") (pin "SHLD8") (pinfunction "SHLD_SHLD8") (pintype "bidirectional"))
    )
    (net (code "64") (name "XSMT") (class "Default")
      (node (ref "IC1") (pin "17") (pinfunction "XSMT_17") (pintype "input"))
      (node (ref "U3") (pin "32") (pinfunction "IO39_32") (pintype "bidirectional"))
    )
    (net (code "65") (name "unconnected-(CON7-PadP$1)") (class "Default")
      (node (ref "CON7") (pin "P$1") (pinfunction "P$1_P$1") (pintype "bidirectional"))
    )
    (net (code "66") (name "unconnected-(CON7-PadP$2)") (class "Default")
      (node (ref "CON7") (pin "P$2") (pinfunction "P$2_P$2") (pintype "bidirectional"))
    )
    (net (code "67") (name "unconnected-(CON7-PadP$3)") (class "Default")
      (node (ref "CON7") (pin "P$3") (pinfunction "P$3_P$3") (pintype "bidirectional"))
    )
    (net (code "68") (name "unconnected-(CON7-PadP$4)") (class "Default")
      (node (ref "CON7") (pin "P$4") (pinfunction "P$4_P$4") (pintype "bidirectional"))
    )
    (net (code "69") (name "unconnected-(CON8-PadP$1)") (class "Default")
      (node (ref "CON8") (pin "P$1") (pinfunction "P$1_P$1") (pintype "bidirectional"))
    )
    (net (code "70") (name "unconnected-(CON8-PadP$2)") (class "Default")
      (node (ref "CON8") (pin "P$2") (pinfunction "P$2_P$2") (pintype "bidirectional"))
    )
    (net (code "71") (name "unconnected-(CON8-PadP$3)") (class "Default")
      (node (ref "CON8") (pin "P$3") (pinfunction "P$3_P$3") (pintype "bidirectional"))
    )
    (net (code "72") (name "unconnected-(CON8-PadP$4)") (class "Default")
      (node (ref "CON8") (pin "P$4") (pinfunction "P$4_P$4") (pintype "bidirectional"))
    )
    (net (code "73") (name "unconnected-(SD1-DAT1-Pad8)") (class "Default")
      (node (ref "SD1") (pin "8") (pinfunction "DAT1_8") (pintype "bidirectional"))
    )
    (net (code "74") (name "unconnected-(SD1-DAT2-Pad1)") (class "Default")
      (node (ref "SD1") (pin "1") (pinfunction "DAT2_1") (pintype "bidirectional"))
    )
    (net (code "75") (name "unconnected-(SD1-~{CARD}-Pad9)") (class "Default")
      (node (ref "SD1") (pin "9") (pinfunction "~{CARD}_9") (pintype "passive"))
    )
  )
)
